# 07-TCXO_Crystal.net
KiCad netlist of a schematic drawn in Altium Designer
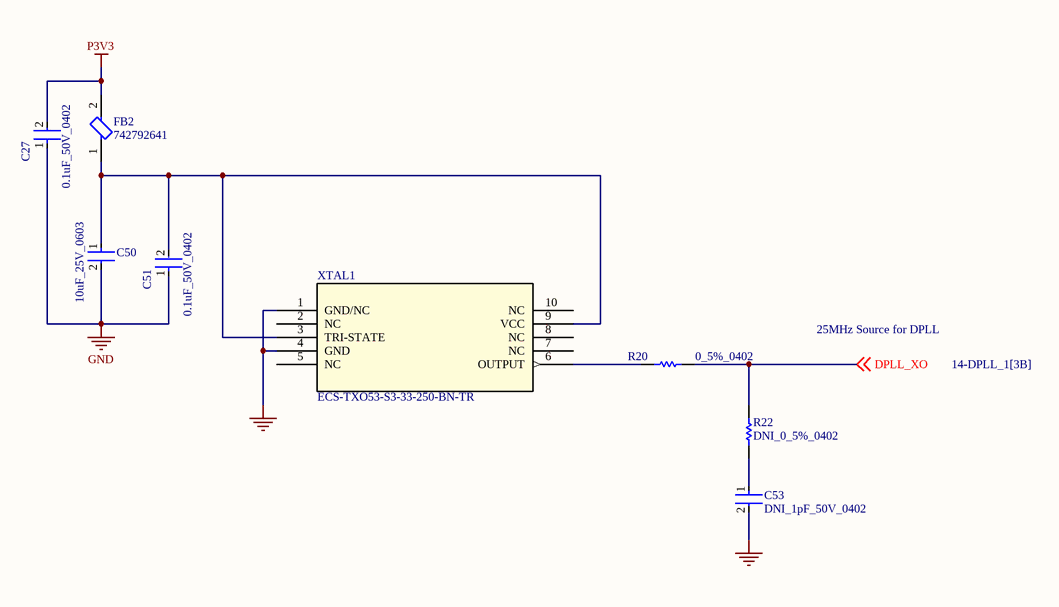
[diagram p0: 07-TCXO_Crystal.SchDoc]

(export (version "E")
  (design (tool "Eeschema 10.0.6"))
  (components
    (comp (ref "C27")
      (value "0.1uF_50V_0402")
      (footprint "FP-C1005-050-0_05-IPC_C")
      (description "Multilayer Ceramic Capacitors 100nF ±10% 50V X7R SMD 0402")
      (fields (field (name "VOLTAGE") "50V") (field (name "TOLERANCE") "10%"))
      (libsource (lib "Altium Content Vault") (part "b4654b650e69147ec39a6b967a45e02"))
    )
    (comp (ref "C50")
      (value "10uF_25V_0603")
      (footprint "FP-CL10-IPC_C")
      (description "Cap Ceramic 10uF 25V X5R ±20% Pad SMD 0603 +85°C T/R")
      (fields (field (name "TOLERANCE") "20%"))
      (libsource (lib "Altium Content Vault") (part "b4654b650e69147ec39a6b967a45e02"))
    )
    (comp (ref "C51")
      (value "0.1uF_50V_0402")
      (footprint "FP-C1005-050-0_05-IPC_C")
      (description "Multilayer Ceramic Capacitors 100nF ±10% 50V X7R SMD 0402")
      (fields (field (name "VOLTAGE") "50V") (field (name "TOLERANCE") "10%"))
      (libsource (lib "Altium Content Vault") (part "b4654b650e69147ec39a6b967a45e02"))
    )
    (comp (ref "C53")
      (value "DNI_1pF_50V_0402")
      (footprint "FP-GJM155-0_05-IPC_B")
      (description "Multi-Layer Ceramic Capacitor 1pF C0G  ±0.1pF 0402 Paper T/R")
      (fields (field (name "VOLTAGE") "50V"))
      (libsource (lib "Altium Content Vault") (part "02cd4be3c70576c341d710602a673aa"))
    )
    (comp (ref "FB2")
      (value "742792641")
      (footprint "FP-742792641-MFG")
      (description "FERRITE BEAD 300 OHM 0603 1LN")
      (fields (field (name "TOLERANCE") "25%"))
      (libsource (lib "Altium Content Vault") (part "5f30dd21d616792df468990f7003faa"))
    )
    (comp (ref "R20")
      (value "0_5%_0402")
      (footprint "RESC1005X40X25NL05T10")
      (fields (field (name "MANUFACTURER") "Panasonic") (field (name "PART NUMBER") "ERJ-U020R00X"))
      (libsource (lib "Altium Content Vault") (part "RES"))
    )
    (comp (ref "R22")
      (value "DNI_0_5%_0402")
      (footprint "RESC1005X40X25NL05T10")
      (fields (field (name "MANUFACTURER") "Panasonic") (field (name "PART NUMBER") "ERJ-U020R00X"))
      (libsource (lib "Altium Content Vault") (part "RES"))
    )
    (comp (ref "XTAL1")
      (value "ECS-TXO53-S3-33-250-BN-TR")
      (footprint "SO10_ECS-TXO_ECS")
      (description "No Description Available")
      (libsource (lib "ECS-TXO53-S3-33-250-BN-TR") (part "ECS-TXO53-S3-33-250-BN-TR"))
    )
  )
  (nets
    (net (code "1") (name "DPLL_XO") (class "Default")
      (node (ref "R20") (pin "2") (pinfunction "2_2") (pintype "passive"))
      (node (ref "R22") (pin "2") (pinfunction "2_2") (pintype "passive"))
    )
    (net (code "2") (name "GND") (class "Default")
      (node (ref "C27") (pin "1") (pinfunction "1_1") (pintype "passive"))
      (node (ref "C50") (pin "2") (pinfunction "2_2") (pintype "passive"))
      (node (ref "C51") (pin "1") (pinfunction "1_1") (pintype "passive"))
      (node (ref "C53") (pin "2") (pinfunction "2_2") (pintype "passive"))
      (node (ref "XTAL1") (pin "1") (pinfunction "GND/NC_1") (pintype "passive"))
      (node (ref "XTAL1") (pin "4") (pinfunction "GND_4") (pintype "power_in"))
    )
    (net (code "3") (name "Net-(C53-Pad1)") (class "Default")
      (node (ref "C53") (pin "1") (pinfunction "1_1") (pintype "passive"))
      (node (ref "R22") (pin "1") (pinfunction "1_1") (pintype "passive"))
    )
    (net (code "4") (name "Net-(XTAL1-OUTPUT)") (class "Default")
      (node (ref "R20") (pin "1") (pinfunction "1_1") (pintype "passive"))
      (node (ref "XTAL1") (pin "6") (pinfunction "OUTPUT_6") (pintype "output"))
    )
    (net (code "5") (name "Net-(XTAL1-TRI-STATE)") (class "Default")
      (node (ref "C50") (pin "1") (pinfunction "1_1") (pintype "passive"))
      (node (ref "C51") (pin "2") (pinfunction "2_2") (pintype "passive"))
      (node (ref "FB2") (pin "1") (pinfunction "1_1") (pintype "passive"))
      (node (ref "XTAL1") (pin "3") (pinfunction "TRI-STATE_3") (pintype "tri_state"))
      (node (ref "XTAL1") (pin "9") (pinfunction "VCC_9") (pintype "power_in"))
    )
    (net (code "6") (name "P3V3") (class "Default")
      (node (ref "C27") (pin "2") (pinfunction "2_2") (pintype "passive"))
      (node (ref "FB2") (pin "2") (pinfunction "2_2") (pintype "passive"))
    )
    (net (code "7") (name "unconnected-(XTAL1-NC-Pad2)") (class "Default")
      (node (ref "XTAL1") (pin "2") (pinfunction "NC_2") (pintype "passive"))
    )
    (net (code "8") (name "unconnected-(XTAL1-NC-Pad5)") (class "Default")
      (node (ref "XTAL1") (pin "5") (pinfunction "NC_5") (pintype "passive"))
    )
    (net (code "9") (name "unconnected-(XTAL1-NC-Pad7)") (class "Default")
      (node (ref "XTAL1") (pin "7") (pinfunction "NC_7") (pintype "passive"))
    )
    (net (code "10") (name "unconnected-(XTAL1-NC-Pad8)") (class "Default")
      (node (ref "XTAL1") (pin "8") (pinfunction "NC_8") (pintype "passive"))
    )
    (net (code "11") (name "unconnected-(XTAL1-NC-Pad10)") (class "Default")
      (node (ref "XTAL1") (pin "10") (pinfunction "NC_10") (pintype "passive"))
    )
  )
)
